# SoC_DDR.net
KiCad netlist of a schematic drawn in Altium Designer
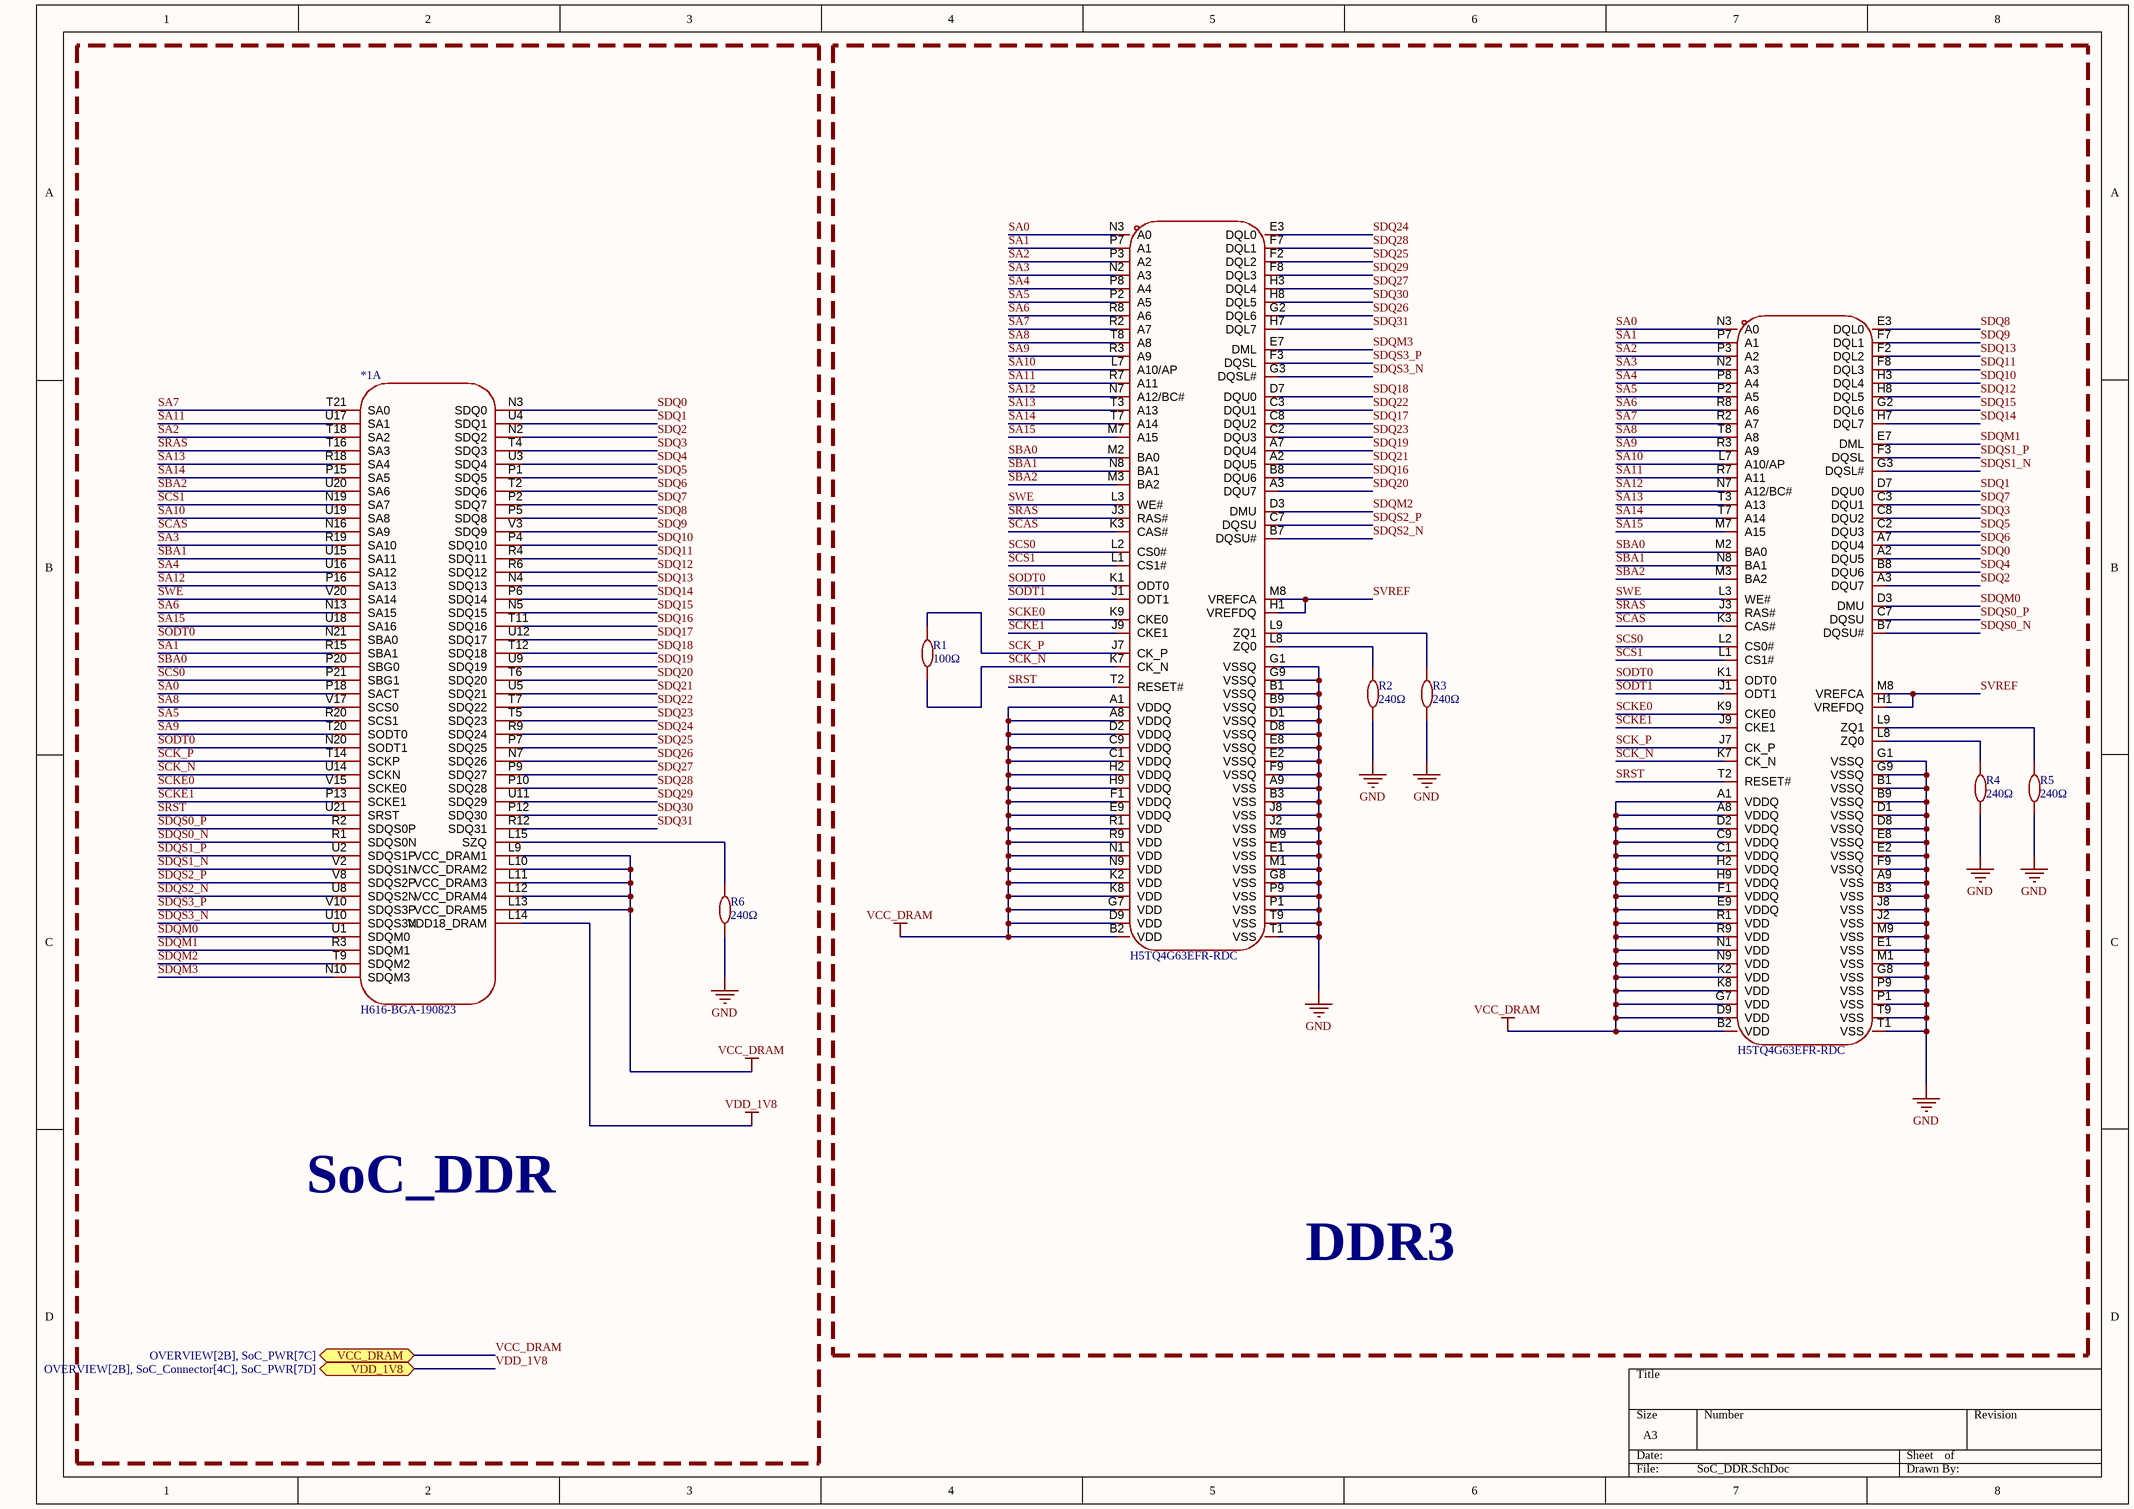
[diagram p0: SoC_DDR.SchDoc]

(export (version "E")
  (design (tool "Eeschema 10.0.6"))
  (components
    (comp (ref "*1")
      (value "H616-BGA-190823")
      (footprint "BGA-284_L14.0-W12.0-P0.65-TL")
      (description "Allwinner H616")
      (libsource (lib "IC") (part "H616-BGA-190823"))
    )
    (comp (ref "R1")
      (value "100Ω")
      (footprint "R0402")
      (description "100Ω 62.5mW 50V ±100ppm/℃ Thick Film Resistor ±1% 0402 Chip Resistor - Surface Mount ROHS")
      (libsource (lib "RLC") (part "100Ω"))
    )
    (comp (ref "R2")
      (value "240Ω")
      (footprint "R0402")
      (description "240Ω 62.5mW 50V ±100ppm/℃ Thick Film Resistor ±1% 0402 Chip Resistor - Surface Mount ROHS")
      (libsource (lib "RLC") (part "240Ω"))
    )
    (comp (ref "R3")
      (value "240Ω")
      (footprint "R0402")
      (description "240Ω 62.5mW 50V ±100ppm/℃ Thick Film Resistor ±1% 0402 Chip Resistor - Surface Mount ROHS")
      (libsource (lib "RLC") (part "240Ω"))
    )
    (comp (ref "R4")
      (value "240Ω")
      (footprint "R0402")
      (description "240Ω 62.5mW 50V ±100ppm/℃ Thick Film Resistor ±1% 0402 Chip Resistor - Surface Mount ROHS")
      (libsource (lib "RLC") (part "240Ω"))
    )
    (comp (ref "R5")
      (value "240Ω")
      (footprint "R0402")
      (description "240Ω 62.5mW 50V ±100ppm/℃ Thick Film Resistor ±1% 0402 Chip Resistor - Surface Mount ROHS")
      (libsource (lib "RLC") (part "240Ω"))
    )
    (comp (ref "R6")
      (value "240Ω")
      (footprint "R0402")
      (description "240Ω 62.5mW 50V ±100ppm/℃ Thick Film Resistor ±1% 0402 Chip Resistor - Surface Mount ROHS")
      (libsource (lib "RLC") (part "240Ω"))
    )
    (comp (ref "U1")
      (value "H5TQ4G63EFR-RDC")
      (footprint "TFBGA-96_L13.0-W7.5-R16-C6-P0.80-TL")
      (description "4Gb DDR3 同步动态随机存取存储器")
      (libsource (lib "IC") (part "H5TQ4G63EFR-RDC"))
    )
    (comp (ref "U2")
      (value "H5TQ4G63EFR-RDC")
      (footprint "TFBGA-96_L13.0-W7.5-R16-C6-P0.80-TL")
      (description "4Gb DDR3 同步动态随机存取存储器")
      (libsource (lib "IC") (part "H5TQ4G63EFR-RDC"))
    )
  )
  (nets
    (net (code "1") (name "/SA0") (class "Default")
      (node (ref "*1") (pin "P18") (pinfunction "SACT_P18") (pintype "passive"))
      (node (ref "U1") (pin "N3") (pinfunction "A0_N3") (pintype "passive"))
      (node (ref "U2") (pin "N3") (pinfunction "A0_N3") (pintype "passive"))
    )
    (net (code "2") (name "/SA1") (class "Default")
      (node (ref "*1") (pin "R15") (pinfunction "SBA1_R15") (pintype "passive"))
      (node (ref "U1") (pin "P7") (pinfunction "A1_P7") (pintype "passive"))
      (node (ref "U2") (pin "P7") (pinfunction "A1_P7") (pintype "passive"))
    )
    (net (code "3") (name "/SA2") (class "Default")
      (node (ref "*1") (pin "T18") (pinfunction "SA2_T18") (pintype "passive"))
      (node (ref "U1") (pin "P3") (pinfunction "A2_P3") (pintype "passive"))
      (node (ref "U2") (pin "P3") (pinfunction "A2_P3") (pintype "passive"))
    )
    (net (code "4") (name "/SA3") (class "Default")
      (node (ref "*1") (pin "R19") (pinfunction "SA10_R19") (pintype "passive"))
      (node (ref "U1") (pin "N2") (pinfunction "A3_N2") (pintype "passive"))
      (node (ref "U2") (pin "N2") (pinfunction "A3_N2") (pintype "passive"))
    )
    (net (code "5") (name "/SA4") (class "Default")
      (node (ref "*1") (pin "U16") (pinfunction "SA12_U16") (pintype "passive"))
      (node (ref "U1") (pin "P8") (pinfunction "A4_P8") (pintype "passive"))
      (node (ref "U2") (pin "P8") (pinfunction "A4_P8") (pintype "passive"))
    )
    (net (code "6") (name "/SA5") (class "Default")
      (node (ref "*1") (pin "R20") (pinfunction "SCS1_R20") (pintype "passive"))
      (node (ref "U1") (pin "P2") (pinfunction "A5_P2") (pintype "passive"))
      (node (ref "U2") (pin "P2") (pinfunction "A5_P2") (pintype "passive"))
    )
    (net (code "7") (name "/SA6") (class "Default")
      (node (ref "*1") (pin "N13") (pinfunction "SA15_N13") (pintype "passive"))
      (node (ref "U1") (pin "R8") (pinfunction "A6_R8") (pintype "passive"))
      (node (ref "U2") (pin "R8") (pinfunction "A6_R8") (pintype "passive"))
    )
    (net (code "8") (name "/SA7") (class "Default")
      (node (ref "*1") (pin "T21") (pinfunction "SA0_T21") (pintype "passive"))
      (node (ref "U1") (pin "R2") (pinfunction "A7_R2") (pintype "passive"))
      (node (ref "U2") (pin "R2") (pinfunction "A7_R2") (pintype "passive"))
    )
    (net (code "9") (name "/SA8") (class "Default")
      (node (ref "*1") (pin "V17") (pinfunction "SCS0_V17") (pintype "passive"))
      (node (ref "U1") (pin "T8") (pinfunction "A8_T8") (pintype "passive"))
      (node (ref "U2") (pin "T8") (pinfunction "A8_T8") (pintype "passive"))
    )
    (net (code "10") (name "/SA9") (class "Default")
      (node (ref "*1") (pin "T20") (pinfunction "SODT0_T20") (pintype "passive"))
      (node (ref "U1") (pin "R3") (pinfunction "A9_R3") (pintype "passive"))
      (node (ref "U2") (pin "R3") (pinfunction "A9_R3") (pintype "passive"))
    )
    (net (code "11") (name "/SA10") (class "Default")
      (node (ref "*1") (pin "U19") (pinfunction "SA8_U19") (pintype "passive"))
      (node (ref "U1") (pin "L7") (pinfunction "A10/AP_L7") (pintype "passive"))
      (node (ref "U2") (pin "L7") (pinfunction "A10/AP_L7") (pintype "passive"))
    )
    (net (code "12") (name "/SA11") (class "Default")
      (node (ref "*1") (pin "U17") (pinfunction "SA1_U17") (pintype "passive"))
      (node (ref "U1") (pin "R7") (pinfunction "A11_R7") (pintype "passive"))
      (node (ref "U2") (pin "R7") (pinfunction "A11_R7") (pintype "passive"))
    )
    (net (code "13") (name "/SA12") (class "Default")
      (node (ref "*1") (pin "P16") (pinfunction "SA13_P16") (pintype "passive"))
      (node (ref "U1") (pin "N7") (pinfunction "A12/BC#_N7") (pintype "passive"))
      (node (ref "U2") (pin "N7") (pinfunction "A12/BC#_N7") (pintype "passive"))
    )
    (net (code "14") (name "/SA13") (class "Default")
      (node (ref "*1") (pin "R18") (pinfunction "SA4_R18") (pintype "passive"))
      (node (ref "U1") (pin "T3") (pinfunction "A13_T3") (pintype "passive"))
      (node (ref "U2") (pin "T3") (pinfunction "A13_T3") (pintype "passive"))
    )
    (net (code "15") (name "/SA14") (class "Default")
      (node (ref "*1") (pin "P15") (pinfunction "SA5_P15") (pintype "passive"))
      (node (ref "U1") (pin "T7") (pinfunction "A14_T7") (pintype "passive"))
      (node (ref "U2") (pin "T7") (pinfunction "A14_T7") (pintype "passive"))
    )
    (net (code "16") (name "/SA15") (class "Default")
      (node (ref "*1") (pin "U18") (pinfunction "SA16_U18") (pintype "passive"))
      (node (ref "U1") (pin "M7") (pinfunction "A15_M7") (pintype "passive"))
      (node (ref "U2") (pin "M7") (pinfunction "A15_M7") (pintype "passive"))
    )
    (net (code "17") (name "/SBA0") (class "Default")
      (node (ref "*1") (pin "P20") (pinfunction "SBG0_P20") (pintype "passive"))
      (node (ref "U1") (pin "M2") (pinfunction "BA0_M2") (pintype "passive"))
      (node (ref "U2") (pin "M2") (pinfunction "BA0_M2") (pintype "passive"))
    )
    (net (code "18") (name "/SBA1") (class "Default")
      (node (ref "*1") (pin "U15") (pinfunction "SA11_U15") (pintype "passive"))
      (node (ref "U1") (pin "N8") (pinfunction "BA1_N8") (pintype "passive"))
      (node (ref "U2") (pin "N8") (pinfunction "BA1_N8") (pintype "passive"))
    )
    (net (code "19") (name "/SBA2") (class "Default")
      (node (ref "*1") (pin "U20") (pinfunction "SA6_U20") (pintype "passive"))
      (node (ref "U1") (pin "M3") (pinfunction "BA2_M3") (pintype "passive"))
      (node (ref "U2") (pin "M3") (pinfunction "BA2_M3") (pintype "passive"))
    )
    (net (code "20") (name "/SCAS") (class "Default")
      (node (ref "*1") (pin "N16") (pinfunction "SA9_N16") (pintype "passive"))
      (node (ref "U1") (pin "K3") (pinfunction "CAS#_K3") (pintype "passive"))
      (node (ref "U2") (pin "K3") (pinfunction "CAS#_K3") (pintype "passive"))
    )
    (net (code "21") (name "/SCKE0") (class "Default")
      (node (ref "*1") (pin "V15") (pinfunction "SCKE0_V15") (pintype "passive"))
      (node (ref "U1") (pin "K9") (pinfunction "CKE0_K9") (pintype "passive"))
      (node (ref "U2") (pin "K9") (pinfunction "CKE0_K9") (pintype "passive"))
    )
    (net (code "22") (name "/SCKE1") (class "Default")
      (node (ref "*1") (pin "P13") (pinfunction "SCKE1_P13") (pintype "passive"))
      (node (ref "U1") (pin "J9") (pinfunction "CKE1_J9") (pintype "passive"))
      (node (ref "U2") (pin "J9") (pinfunction "CKE1_J9") (pintype "passive"))
    )
    (net (code "23") (name "/SCK_N") (class "Default")
      (node (ref "*1") (pin "U14") (pinfunction "SCKN_U14") (pintype "passive"))
      (node (ref "R1") (pin "1") (pinfunction "1_1") (pintype "passive"))
      (node (ref "U1") (pin "K7") (pinfunction "CK_N_K7") (pintype "passive"))
      (node (ref "U2") (pin "K7") (pinfunction "CK_N_K7") (pintype "passive"))
    )
    (net (code "24") (name "/SCK_P") (class "Default")
      (node (ref "*1") (pin "T14") (pinfunction "SCKP_T14") (pintype "passive"))
      (node (ref "R1") (pin "2") (pinfunction "2_2") (pintype "passive"))
      (node (ref "U1") (pin "J7") (pinfunction "CK_P_J7") (pintype "passive"))
      (node (ref "U2") (pin "J7") (pinfunction "CK_P_J7") (pintype "passive"))
    )
    (net (code "25") (name "/SCS0") (class "Default")
      (node (ref "*1") (pin "P21") (pinfunction "SBG1_P21") (pintype "passive"))
      (node (ref "U1") (pin "L2") (pinfunction "CS0#_L2") (pintype "passive"))
      (node (ref "U2") (pin "L2") (pinfunction "CS0#_L2") (pintype "passive"))
    )
    (net (code "26") (name "/SCS1") (class "Default")
      (node (ref "*1") (pin "N19") (pinfunction "SA7_N19") (pintype "passive"))
      (node (ref "U1") (pin "L1") (pinfunction "CS1#_L1") (pintype "passive"))
      (node (ref "U2") (pin "L1") (pinfunction "CS1#_L1") (pintype "passive"))
    )
    (net (code "27") (name "/SDQ0") (class "Default")
      (node (ref "*1") (pin "N3") (pinfunction "SDQ0_N3") (pintype "passive"))
      (node (ref "U2") (pin "A2") (pinfunction "DQU5_A2") (pintype "passive"))
    )
    (net (code "28") (name "/SDQ1") (class "Default")
      (node (ref "*1") (pin "U4") (pinfunction "SDQ1_U4") (pintype "passive"))
      (node (ref "U2") (pin "D7") (pinfunction "DQU0_D7") (pintype "passive"))
    )
    (net (code "29") (name "/SDQ2") (class "Default")
      (node (ref "*1") (pin "N2") (pinfunction "SDQ2_N2") (pintype "passive"))
      (node (ref "U2") (pin "A3") (pinfunction "DQU7_A3") (pintype "passive"))
    )
    (net (code "30") (name "/SDQ3") (class "Default")
      (node (ref "*1") (pin "T4") (pinfunction "SDQ3_T4") (pintype "passive"))
      (node (ref "U2") (pin "C8") (pinfunction "DQU2_C8") (pintype "passive"))
    )
    (net (code "31") (name "/SDQ4") (class "Default")
      (node (ref "*1") (pin "U3") (pinfunction "SDQ4_U3") (pintype "passive"))
      (node (ref "U2") (pin "B8") (pinfunction "DQU6_B8") (pintype "passive"))
    )
    (net (code "32") (name "/SDQ5") (class "Default")
      (node (ref "*1") (pin "P1") (pinfunction "SDQ5_P1") (pintype "passive"))
      (node (ref "U2") (pin "C2") (pinfunction "DQU3_C2") (pintype "passive"))
    )
    (net (code "33") (name "/SDQ6") (class "Default")
      (node (ref "*1") (pin "T2") (pinfunction "SDQ6_T2") (pintype "passive"))
      (node (ref "U2") (pin "A7") (pinfunction "DQU4_A7") (pintype "passive"))
    )
    (net (code "34") (name "/SDQ7") (class "Default")
      (node (ref "*1") (pin "P2") (pinfunction "SDQ7_P2") (pintype "passive"))
      (node (ref "U2") (pin "C3") (pinfunction "DQU1_C3") (pintype "passive"))
    )
    (net (code "35") (name "/SDQ8") (class "Default")
      (node (ref "*1") (pin "P5") (pinfunction "SDQ8_P5") (pintype "passive"))
      (node (ref "U2") (pin "E3") (pinfunction "DQL0_E3") (pintype "passive"))
    )
    (net (code "36") (name "/SDQ9") (class "Default")
      (node (ref "*1") (pin "V3") (pinfunction "SDQ9_V3") (pintype "passive"))
      (node (ref "U2") (pin "F7") (pinfunction "DQL1_F7") (pintype "passive"))
    )
    (net (code "37") (name "/SDQ10") (class "Default")
      (node (ref "*1") (pin "P4") (pinfunction "SDQ10_P4") (pintype "passive"))
      (node (ref "U2") (pin "H3") (pinfunction "DQL4_H3") (pintype "passive"))
    )
    (net (code "38") (name "/SDQ11") (class "Default")
      (node (ref "*1") (pin "R4") (pinfunction "SDQ11_R4") (pintype "passive"))
      (node (ref "U2") (pin "F8") (pinfunction "DQL3_F8") (pintype "passive"))
    )
    (net (code "39") (name "/SDQ12") (class "Default")
      (node (ref "*1") (pin "R6") (pinfunction "SDQ12_R6") (pintype "passive"))
      (node (ref "U2") (pin "H8") (pinfunction "DQL5_H8") (pintype "passive"))
    )
    (net (code "40") (name "/SDQ13") (class "Default")
      (node (ref "*1") (pin "N4") (pinfunction "SDQ13_N4") (pintype "passive"))
      (node (ref "U2") (pin "F2") (pinfunction "DQL2_F2") (pintype "passive"))
    )
    (net (code "41") (name "/SDQ14") (class "Default")
      (node (ref "*1") (pin "P6") (pinfunction "SDQ14_P6") (pintype "passive"))
      (node (ref "U2") (pin "H7") (pinfunction "DQL7_H7") (pintype "passive"))
    )
    (net (code "42") (name "/SDQ15") (class "Default")
      (node (ref "*1") (pin "N5") (pinfunction "SDQ15_N5") (pintype "passive"))
      (node (ref "U2") (pin "G2") (pinfunction "DQL6_G2") (pintype "passive"))
    )
    (net (code "43") (name "/SDQ16") (class "Default")
      (node (ref "*1") (pin "T11") (pinfunction "SDQ16_T11") (pintype "passive"))
      (node (ref "U1") (pin "B8") (pinfunction "DQU6_B8") (pintype "passive"))
    )
    (net (code "44") (name "/SDQ17") (class "Default")
      (node (ref "*1") (pin "U12") (pinfunction "SDQ17_U12") (pintype "passive"))
      (node (ref "U1") (pin "C8") (pinfunction "DQU2_C8") (pintype "passive"))
    )
    (net (code "45") (name "/SDQ18") (class "Default")
      (node (ref "*1") (pin "T12") (pinfunction "SDQ18_T12") (pintype "passive"))
      (node (ref "U1") (pin "D7") (pinfunction "DQU0_D7") (pintype "passive"))
    )
    (net (code "46") (name "/SDQ19") (class "Default")
      (node (ref "*1") (pin "U9") (pinfunction "SDQ19_U9") (pintype "passive"))
      (node (ref "U1") (pin "A7") (pinfunction "DQU4_A7") (pintype "passive"))
    )
    (net (code "47") (name "/SDQ20") (class "Default")
      (node (ref "*1") (pin "T6") (pinfunction "SDQ20_T6") (pintype "passive"))
      (node (ref "U1") (pin "A3") (pinfunction "DQU7_A3") (pintype "passive"))
    )
    (net (code "48") (name "/SDQ21") (class "Default")
      (node (ref "*1") (pin "U5") (pinfunction "SDQ21_U5") (pintype "passive"))
      (node (ref "U1") (pin "A2") (pinfunction "DQU5_A2") (pintype "passive"))
    )
    (net (code "49") (name "/SDQ22") (class "Default")
      (node (ref "*1") (pin "T7") (pinfunction "SDQ22_T7") (pintype "passive"))
      (node (ref "U1") (pin "C3") (pinfunction "DQU1_C3") (pintype "passive"))
    )
    (net (code "50") (name "/SDQ23") (class "Default")
      (node (ref "*1") (pin "T5") (pinfunction "SDQ23_T5") (pintype "passive"))
      (node (ref "U1") (pin "C2") (pinfunction "DQU3_C2") (pintype "passive"))
    )
    (net (code "51") (name "/SDQ24") (class "Default")
      (node (ref "*1") (pin "R9") (pinfunction "SDQ24_R9") (pintype "passive"))
      (node (ref "U1") (pin "E3") (pinfunction "DQL0_E3") (pintype "passive"))
    )
    (net (code "52") (name "/SDQ25") (class "Default")
      (node (ref "*1") (pin "P7") (pinfunction "SDQ25_P7") (pintype "passive"))
      (node (ref "U1") (pin "F2") (pinfunction "DQL2_F2") (pintype "passive"))
    )
    (net (code "53") (name "/SDQ26") (class "Default")
      (node (ref "*1") (pin "N7") (pinfunction "SDQ26_N7") (pintype "passive"))
      (node (ref "U1") (pin "G2") (pinfunction "DQL6_G2") (pintype "passive"))
    )
    (net (code "54") (name "/SDQ27") (class "Default")
      (node (ref "*1") (pin "P9") (pinfunction "SDQ27_P9") (pintype "passive"))
      (node (ref "U1") (pin "H3") (pinfunction "DQL4_H3") (pintype "passive"))
    )
    (net (code "55") (name "/SDQ28") (class "Default")
      (node (ref "*1") (pin "P10") (pinfunction "SDQ28_P10") (pintype "passive"))
      (node (ref "U1") (pin "F7") (pinfunction "DQL1_F7") (pintype "passive"))
    )
    (net (code "56") (name "/SDQ29") (class "Default")
      (node (ref "*1") (pin "U11") (pinfunction "SDQ29_U11") (pintype "passive"))
      (node (ref "U1") (pin "F8") (pinfunction "DQL3_F8") (pintype "passive"))
    )
    (net (code "57") (name "/SDQ30") (class "Default")
      (node (ref "*1") (pin "P12") (pinfunction "SDQ30_P12") (pintype "passive"))
      (node (ref "U1") (pin "H8") (pinfunction "DQL5_H8") (pintype "passive"))
    )
    (net (code "58") (name "/SDQ31") (class "Default")
      (node (ref "*1") (pin "R12") (pinfunction "SDQ31_R12") (pintype "passive"))
      (node (ref "U1") (pin "H7") (pinfunction "DQL7_H7") (pintype "passive"))
    )
    (net (code "59") (name "/SDQM0") (class "Default")
      (node (ref "*1") (pin "U1") (pinfunction "SDQM0_U1") (pintype "passive"))
      (node (ref "U2") (pin "D3") (pinfunction "DMU_D3") (pintype "passive"))
    )
    (net (code "60") (name "/SDQM1") (class "Default")
      (node (ref "*1") (pin "R3") (pinfunction "SDQM1_R3") (pintype "passive"))
      (node (ref "U2") (pin "E7") (pinfunction "DML_E7") (pintype "passive"))
    )
    (net (code "61") (name "/SDQM2") (class "Default")
      (node (ref "*1") (pin "T9") (pinfunction "SDQM2_T9") (pintype "passive"))
      (node (ref "U1") (pin "D3") (pinfunction "DMU_D3") (pintype "passive"))
    )
    (net (code "62") (name "/SDQM3") (class "Default")
      (node (ref "*1") (pin "N10") (pinfunction "SDQM3_N10") (pintype "passive"))
      (node (ref "U1") (pin "E7") (pinfunction "DML_E7") (pintype "passive"))
    )
    (net (code "63") (name "/SDQS0_N") (class "Default")
      (node (ref "*1") (pin "R1") (pinfunction "SDQS0N_R1") (pintype "passive"))
      (node (ref "U2") (pin "B7") (pinfunction "DQSU#_B7") (pintype "passive"))
    )
    (net (code "64") (name "/SDQS0_P") (class "Default")
      (node (ref "*1") (pin "R2") (pinfunction "SDQS0P_R2") (pintype "passive"))
      (node (ref "U2") (pin "C7") (pinfunction "DQSU_C7") (pintype "passive"))
    )
    (net (code "65") (name "/SDQS1_N") (class "Default")
      (node (ref "*1") (pin "V2") (pinfunction "SDQS1N_V2") (pintype "passive"))
      (node (ref "U2") (pin "G3") (pinfunction "DQSL#_G3") (pintype "passive"))
    )
    (net (code "66") (name "/SDQS1_P") (class "Default")
      (node (ref "*1") (pin "U2") (pinfunction "SDQS1P_U2") (pintype "passive"))
      (node (ref "U2") (pin "F3") (pinfunction "DQSL_F3") (pintype "passive"))
    )
    (net (code "67") (name "/SDQS2_N") (class "Default")
      (node (ref "*1") (pin "U8") (pinfunction "SDQS2N_U8") (pintype "passive"))
      (node (ref "U1") (pin "B7") (pinfunction "DQSU#_B7") (pintype "passive"))
    )
    (net (code "68") (name "/SDQS2_P") (class "Default")
      (node (ref "*1") (pin "V8") (pinfunction "SDQS2P_V8") (pintype "passive"))
      (node (ref "U1") (pin "C7") (pinfunction "DQSU_C7") (pintype "passive"))
    )
    (net (code "69") (name "/SDQS3_N") (class "Default")
      (node (ref "*1") (pin "U10") (pinfunction "SDQS3N_U10") (pintype "passive"))
      (node (ref "U1") (pin "G3") (pinfunction "DQSL#_G3") (pintype "passive"))
    )
    (net (code "70") (name "/SDQS3_P") (class "Default")
      (node (ref "*1") (pin "V10") (pinfunction "SDQS3P_V10") (pintype "passive"))
      (node (ref "U1") (pin "F3") (pinfunction "DQSL_F3") (pintype "passive"))
    )
    (net (code "71") (name "/SODT0") (class "Default")
      (node (ref "*1") (pin "N20") (pinfunction "SODT1_N20") (pintype "passive"))
      (node (ref "*1") (pin "N21") (pinfunction "SBA0_N21") (pintype "passive"))
      (node (ref "U1") (pin "K1") (pinfunction "ODT0_K1") (pintype "passive"))
      (node (ref "U2") (pin "K1") (pinfunction "ODT0_K1") (pintype "passive"))
    )
    (net (code "72") (name "/SODT1") (class "Default")
      (node (ref "U1") (pin "J1") (pinfunction "ODT1_J1") (pintype "passive"))
      (node (ref "U2") (pin "J1") (pinfunction "ODT1_J1") (pintype "passive"))
    )
    (net (code "73") (name "/SRAS") (class "Default")
      (node (ref "*1") (pin "T16") (pinfunction "SA3_T16") (pintype "passive"))
      (node (ref "U1") (pin "J3") (pinfunction "RAS#_J3") (pintype "passive"))
      (node (ref "U2") (pin "J3") (pinfunction "RAS#_J3") (pintype "passive"))
    )
    (net (code "74") (name "/SRST") (class "Default")
      (node (ref "*1") (pin "U21") (pinfunction "SRST_U21") (pintype "passive"))
      (node (ref "U1") (pin "T2") (pinfunction "RESET#_T2") (pintype "passive"))
      (node (ref "U2") (pin "T2") (pinfunction "RESET#_T2") (pintype "passive"))
    )
    (net (code "75") (name "/SVREF") (class "Default")
      (node (ref "U1") (pin "H1") (pinfunction "VREFDQ_H1") (pintype "passive"))
      (node (ref "U1") (pin "M8") (pinfunction "VREFCA_M8") (pintype "passive"))
      (node (ref "U2") (pin "H1") (pinfunction "VREFDQ_H1") (pintype "passive"))
      (node (ref "U2") (pin "M8") (pinfunction "VREFCA_M8") (pintype "passive"))
    )
    (net (code "76") (name "/SWE") (class "Default")
      (node (ref "*1") (pin "V20") (pinfunction "SA14_V20") (pintype "passive"))
      (node (ref "U1") (pin "L3") (pinfunction "WE#_L3") (pintype "passive"))
      (node (ref "U2") (pin "L3") (pinfunction "WE#_L3") (pintype "passive"))
    )
    (net (code "77") (name "GND") (class "Default")
      (node (ref "R2") (pin "1") (pinfunction "1_1") (pintype "passive"))
      (node (ref "R3") (pin "1") (pinfunction "1_1") (pintype "passive"))
      (node (ref "R4") (pin "1") (pinfunction "1_1") (pintype "passive"))
      (node (ref "R5") (pin "1") (pinfunction "1_1") (pintype "passive"))
      (node (ref "R6") (pin "1") (pinfunction "1_1") (pintype "passive"))
      (node (ref "U1") (pin "A9") (pinfunction "VSS_A9") (pintype "passive"))
      (node (ref "U1") (pin "B1") (pinfunction "VSSQ_B1") (pintype "passive"))
      (node (ref "U1") (pin "B3") (pinfunction "VSS_B3") (pintype "passive"))
      (node (ref "U1") (pin "B9") (pinfunction "VSSQ_B9") (pintype "passive"))
      (node (ref "U1") (pin "D1") (pinfunction "VSSQ_D1") (pintype "passive"))
      (node (ref "U1") (pin "D8") (pinfunction "VSSQ_D8") (pintype "passive"))
      (node (ref "U1") (pin "E1") (pinfunction "VSS_E1") (pintype "passive"))
      (node (ref "U1") (pin "E2") (pinfunction "VSSQ_E2") (pintype "passive"))
      (node (ref "U1") (pin "E8") (pinfunction "VSSQ_E8") (pintype "passive"))
      (node (ref "U1") (pin "F9") (pinfunction "VSSQ_F9") (pintype "passive"))
      (node (ref "U1") (pin "G1") (pinfunction "VSSQ_G1") (pintype "passive"))
      (node (ref "U1") (pin "G8") (pinfunction "VSS_G8") (pintype "passive"))
      (node (ref "U1") (pin "G9") (pinfunction "VSSQ_G9") (pintype "passive"))
      (node (ref "U1") (pin "J2") (pinfunction "VSS_J2") (pintype "passive"))
      (node (ref "U1") (pin "J8") (pinfunction "VSS_J8") (pintype "passive"))
      (node (ref "U1") (pin "M1") (pinfunction "VSS_M1") (pintype "passive"))
      (node (ref "U1") (pin "M9") (pinfunction "VSS_M9") (pintype "passive"))
      (node (ref "U1") (pin "P1") (pinfunction "VSS_P1") (pintype "passive"))
      (node (ref "U1") (pin "P9") (pinfunction "VSS_P9") (pintype "passive"))
      (node (ref "U1") (pin "T1") (pinfunction "VSS_T1") (pintype "passive"))
      (node (ref "U1") (pin "T9") (pinfunction "VSS_T9") (pintype "passive"))
      (node (ref "U2") (pin "A9") (pinfunction "VSS_A9") (pintype "passive"))
      (node (ref "U2") (pin "B1") (pinfunction "VSSQ_B1") (pintype "passive"))
      (node (ref "U2") (pin "B3") (pinfunction "VSS_B3") (pintype "passive"))
      (node (ref "U2") (pin "B9") (pinfunction "VSSQ_B9") (pintype "passive"))
      (node (ref "U2") (pin "D1") (pinfunction "VSSQ_D1") (pintype "passive"))
      (node (ref "U2") (pin "D8") (pinfunction "VSSQ_D8") (pintype "passive"))
      (node (ref "U2") (pin "E1") (pinfunction "VSS_E1") (pintype "passive"))
      (node (ref "U2") (pin "E2") (pinfunction "VSSQ_E2") (pintype "passive"))
      (node (ref "U2") (pin "E8") (pinfunction "VSSQ_E8") (pintype "passive"))
      (node (ref "U2") (pin "F9") (pinfunction "VSSQ_F9") (pintype "passive"))
      (node (ref "U2") (pin "G1") (pinfunction "VSSQ_G1") (pintype "passive"))
      (node (ref "U2") (pin "G8") (pinfunction "VSS_G8") (pintype "passive"))
      (node (ref "U2") (pin "G9") (pinfunction "VSSQ_G9") (pintype "passive"))
      (node (ref "U2") (pin "J2") (pinfunction "VSS_J2") (pintype "passive"))
      (node (ref "U2") (pin "J8") (pinfunction "VSS_J8") (pintype "passive"))
      (node (ref "U2") (pin "M1") (pinfunction "VSS_M1") (pintype "passive"))
      (node (ref "U2") (pin "M9") (pinfunction "VSS_M9") (pintype "passive"))
      (node (ref "U2") (pin "P1") (pinfunction "VSS_P1") (pintype "passive"))
      (node (ref "U2") (pin "P9") (pinfunction "VSS_P9") (pintype "passive"))
      (node (ref "U2") (pin "T1") (pinfunction "VSS_T1") (pintype "passive"))
      (node (ref "U2") (pin "T9") (pinfunction "VSS_T9") (pintype "passive"))
    )
    (net (code "78") (name "Net-(*1A-SZQ)") (class "Default")
      (node (ref "*1") (pin "L15") (pinfunction "SZQ_L15") (pintype "passive"))
      (node (ref "R6") (pin "2") (pinfunction "2_2") (pintype "passive"))
    )
    (net (code "79") (name "Net-(U1-ZQ0)") (class "Default")
      (node (ref "R2") (pin "2") (pinfunction "2_2") (pintype "passive"))
      (node (ref "U1") (pin "L8") (pinfunction "ZQ0_L8") (pintype "passive"))
    )
    (net (code "80") (name "Net-(U1-ZQ1)") (class "Default")
      (node (ref "R3") (pin "2") (pinfunction "2_2") (pintype "passive"))
      (node (ref "U1") (pin "L9") (pinfunction "ZQ1_L9") (pintype "passive"))
    )
    (net (code "81") (name "Net-(U2-ZQ0)") (class "Default")
      (node (ref "R4") (pin "2") (pinfunction "2_2") (pintype "passive"))
      (node (ref "U2") (pin "L8") (pinfunction "ZQ0_L8") (pintype "passive"))
    )
    (net (code "82") (name "Net-(U2-ZQ1)") (class "Default")
      (node (ref "R5") (pin "2") (pinfunction "2_2") (pintype "passive"))
      (node (ref "U2") (pin "L9") (pinfunction "ZQ1_L9") (pintype "passive"))
    )
    (net (code "83") (name "VCC_DRAM") (class "Default")
      (node (ref "*1") (pin "L10") (pinfunction "VCC_DRAM2_L10") (pintype "passive"))
      (node (ref "*1") (pin "L11") (pinfunction "VCC_DRAM3_L11") (pintype "passive"))
      (node (ref "*1") (pin "L12") (pinfunction "VCC_DRAM4_L12") (pintype "passive"))
      (node (ref "*1") (pin "L13") (pinfunction "VCC_DRAM5_L13") (pintype "passive"))
      (node (ref "*1") (pin "L9") (pinfunction "VCC_DRAM1_L9") (pintype "passive"))
      (node (ref "U1") (pin "A1") (pinfunction "VDDQ_A1") (pintype "passive"))
      (node (ref "U1") (pin "A8") (pinfunction "VDDQ_A8") (pintype "passive"))
      (node (ref "U1") (pin "B2") (pinfunction "VDD_B2") (pintype "passive"))
      (node (ref "U1") (pin "C1") (pinfunction "VDDQ_C1") (pintype "passive"))
      (node (ref "U1") (pin "C9") (pinfunction "VDDQ_C9") (pintype "passive"))
      (node (ref "U1") (pin "D2") (pinfunction "VDDQ_D2") (pintype "passive"))
      (node (ref "U1") (pin "D9") (pinfunction "VDD_D9") (pintype "passive"))
      (node (ref "U1") (pin "E9") (pinfunction "VDDQ_E9") (pintype "passive"))
      (node (ref "U1") (pin "F1") (pinfunction "VDDQ_F1") (pintype "passive"))
      (node (ref "U1") (pin "G7") (pinfunction "VDD_G7") (pintype "passive"))
      (node (ref "U1") (pin "H2") (pinfunction "VDDQ_H2") (pintype "passive"))
      (node (ref "U1") (pin "H9") (pinfunction "VDDQ_H9") (pintype "passive"))
      (node (ref "U1") (pin "K2") (pinfunction "VDD_K2") (pintype "passive"))
      (node (ref "U1") (pin "K8") (pinfunction "VDD_K8") (pintype "passive"))
      (node (ref "U1") (pin "N1") (pinfunction "VDD_N1") (pintype "passive"))
      (node (ref "U1") (pin "N9") (pinfunction "VDD_N9") (pintype "passive"))
      (node (ref "U1") (pin "R1") (pinfunction "VDD_R1") (pintype "passive"))
      (node (ref "U1") (pin "R9") (pinfunction "VDD_R9") (pintype "passive"))
      (node (ref "U2") (pin "A1") (pinfunction "VDDQ_A1") (pintype "passive"))
      (node (ref "U2") (pin "A8") (pinfunction "VDDQ_A8") (pintype "passive"))
      (node (ref "U2") (pin "B2") (pinfunction "VDD_B2") (pintype "passive"))
      (node (ref "U2") (pin "C1") (pinfunction "VDDQ_C1") (pintype "passive"))
      (node (ref "U2") (pin "C9") (pinfunction "VDDQ_C9") (pintype "passive"))
      (node (ref "U2") (pin "D2") (pinfunction "VDDQ_D2") (pintype "passive"))
      (node (ref "U2") (pin "D9") (pinfunction "VDD_D9") (pintype "passive"))
      (node (ref "U2") (pin "E9") (pinfunction "VDDQ_E9") (pintype "passive"))
      (node (ref "U2") (pin "F1") (pinfunction "VDDQ_F1") (pintype "passive"))
      (node (ref "U2") (pin "G7") (pinfunction "VDD_G7") (pintype "passive"))
      (node (ref "U2") (pin "H2") (pinfunction "VDDQ_H2") (pintype "passive"))
      (node (ref "U2") (pin "H9") (pinfunction "VDDQ_H9") (pintype "passive"))
      (node (ref "U2") (pin "K2") (pinfunction "VDD_K2") (pintype "passive"))
      (node (ref "U2") (pin "K8") (pinfunction "VDD_K8") (pintype "passive"))
      (node (ref "U2") (pin "N1") (pinfunction "VDD_N1") (pintype "passive"))
      (node (ref "U2") (pin "N9") (pinfunction "VDD_N9") (pintype "passive"))
      (node (ref "U2") (pin "R1") (pinfunction "VDD_R1") (pintype "passive"))
      (node (ref "U2") (pin "R9") (pinfunction "VDD_R9") (pintype "passive"))
    )
    (net (code "84") (name "VDD_1V8") (class "Default")
      (node (ref "*1") (pin "L14") (pinfunction "VDD18_DRAM_L14") (pintype "passive"))
    )
  )
)
